# mini-v1_14-macrofab-rtg.net
KiCad netlist of a schematic drawn in EAGLE
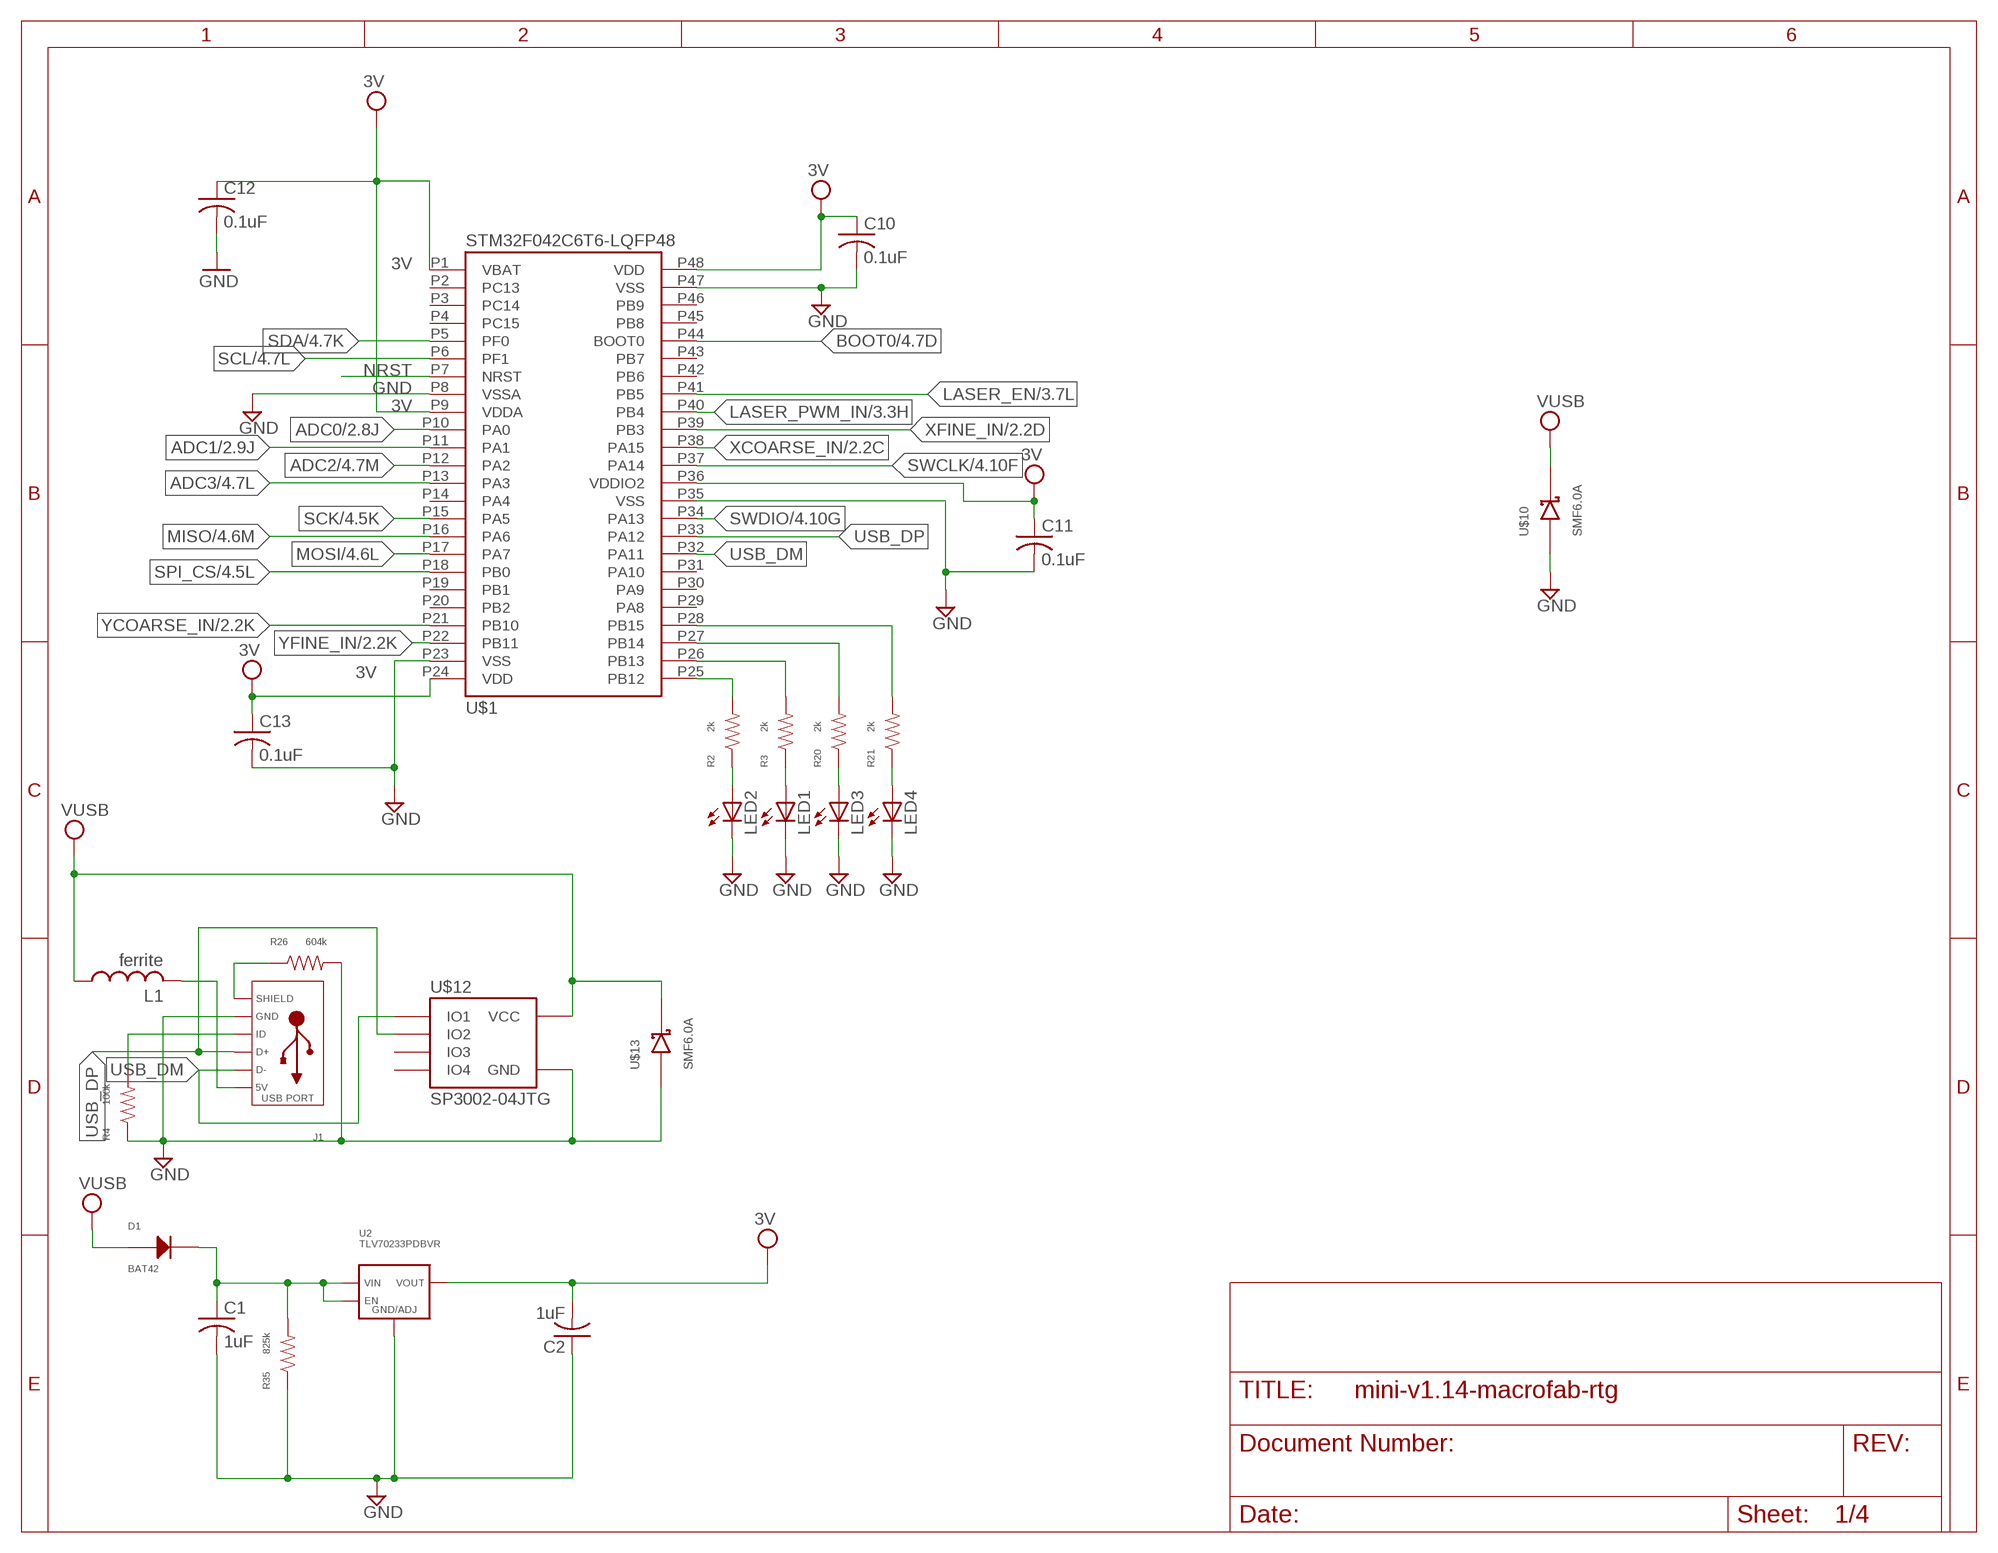
[diagram p0: schematic, sheet 1]
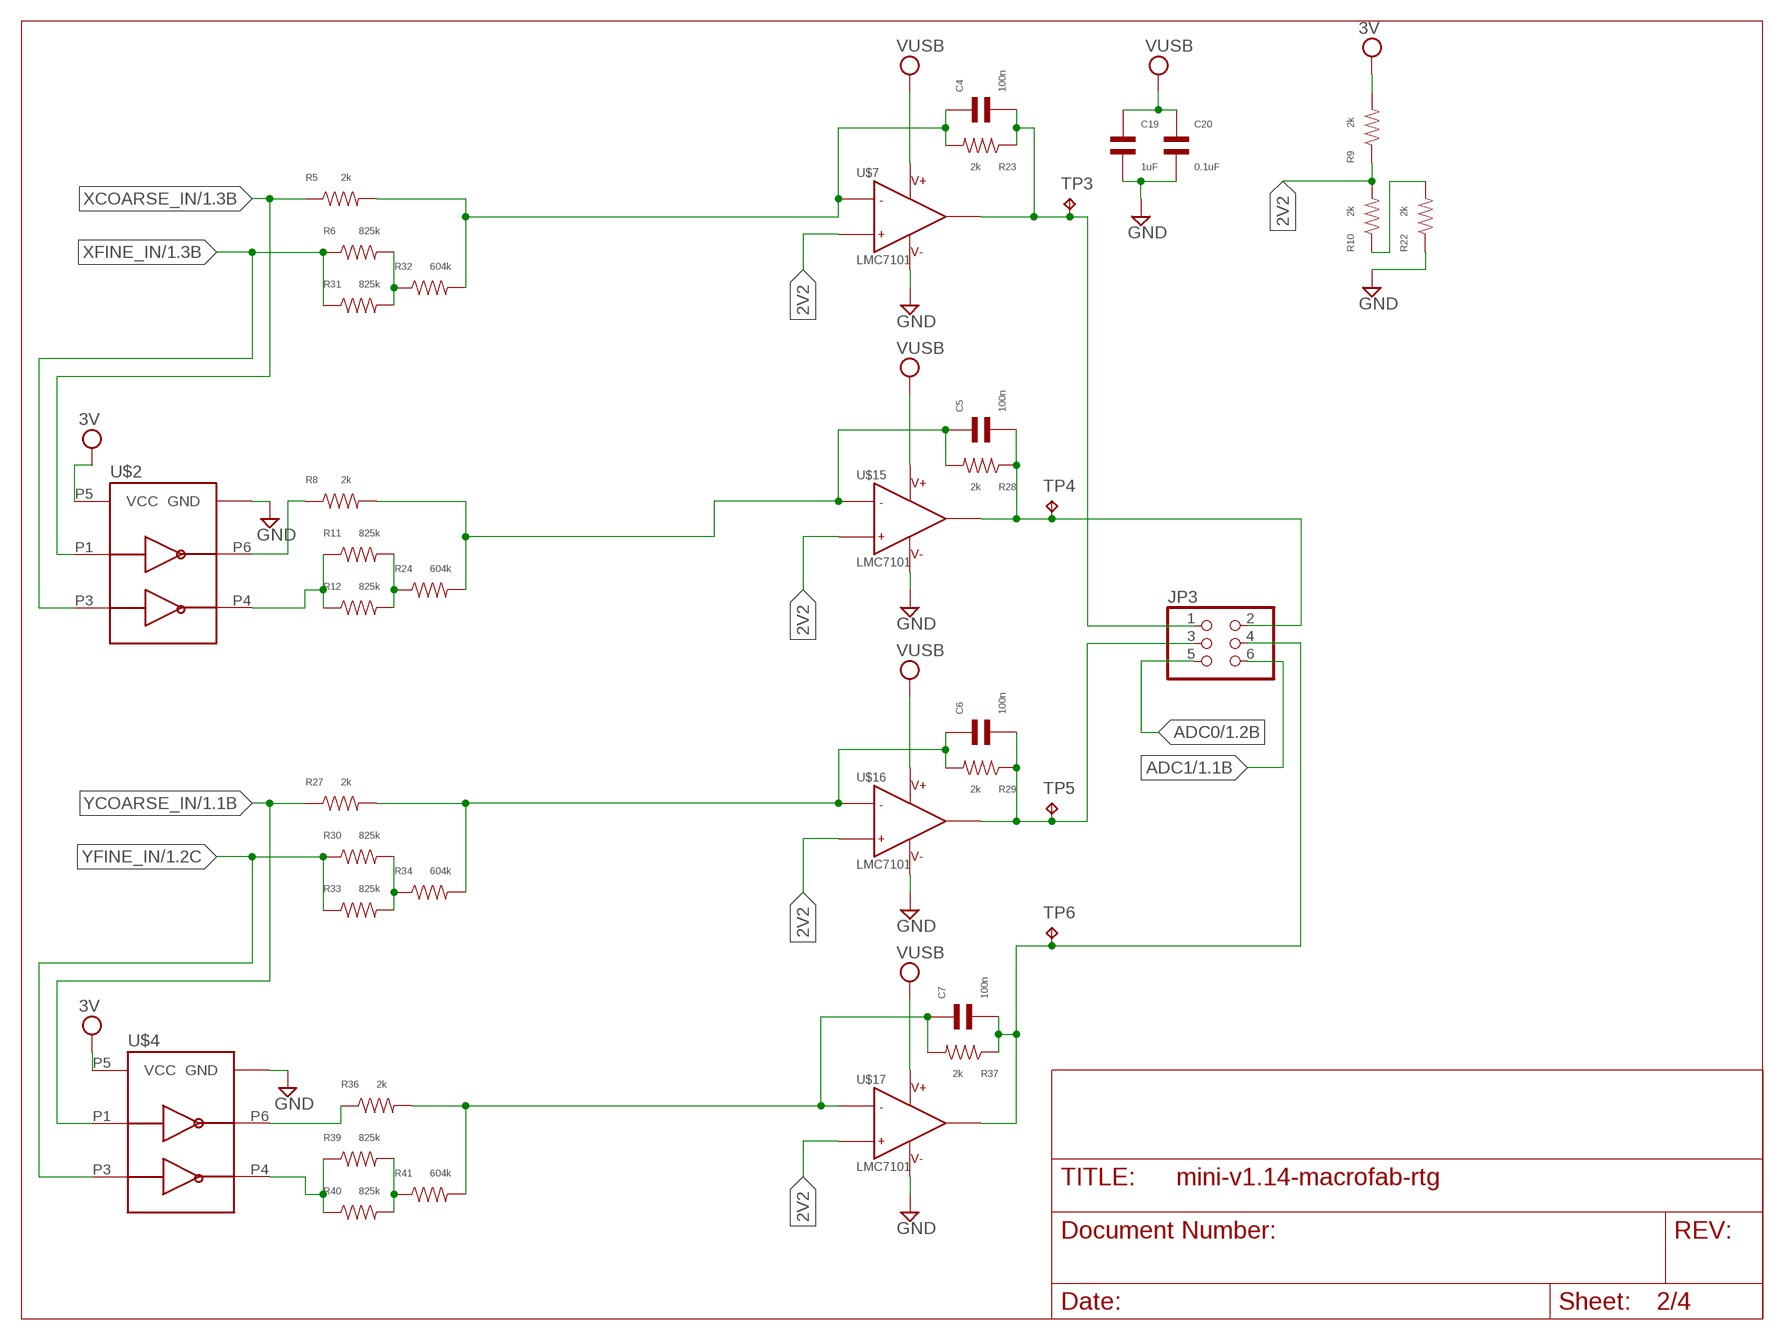
[diagram p1: schematic, sheet 2]
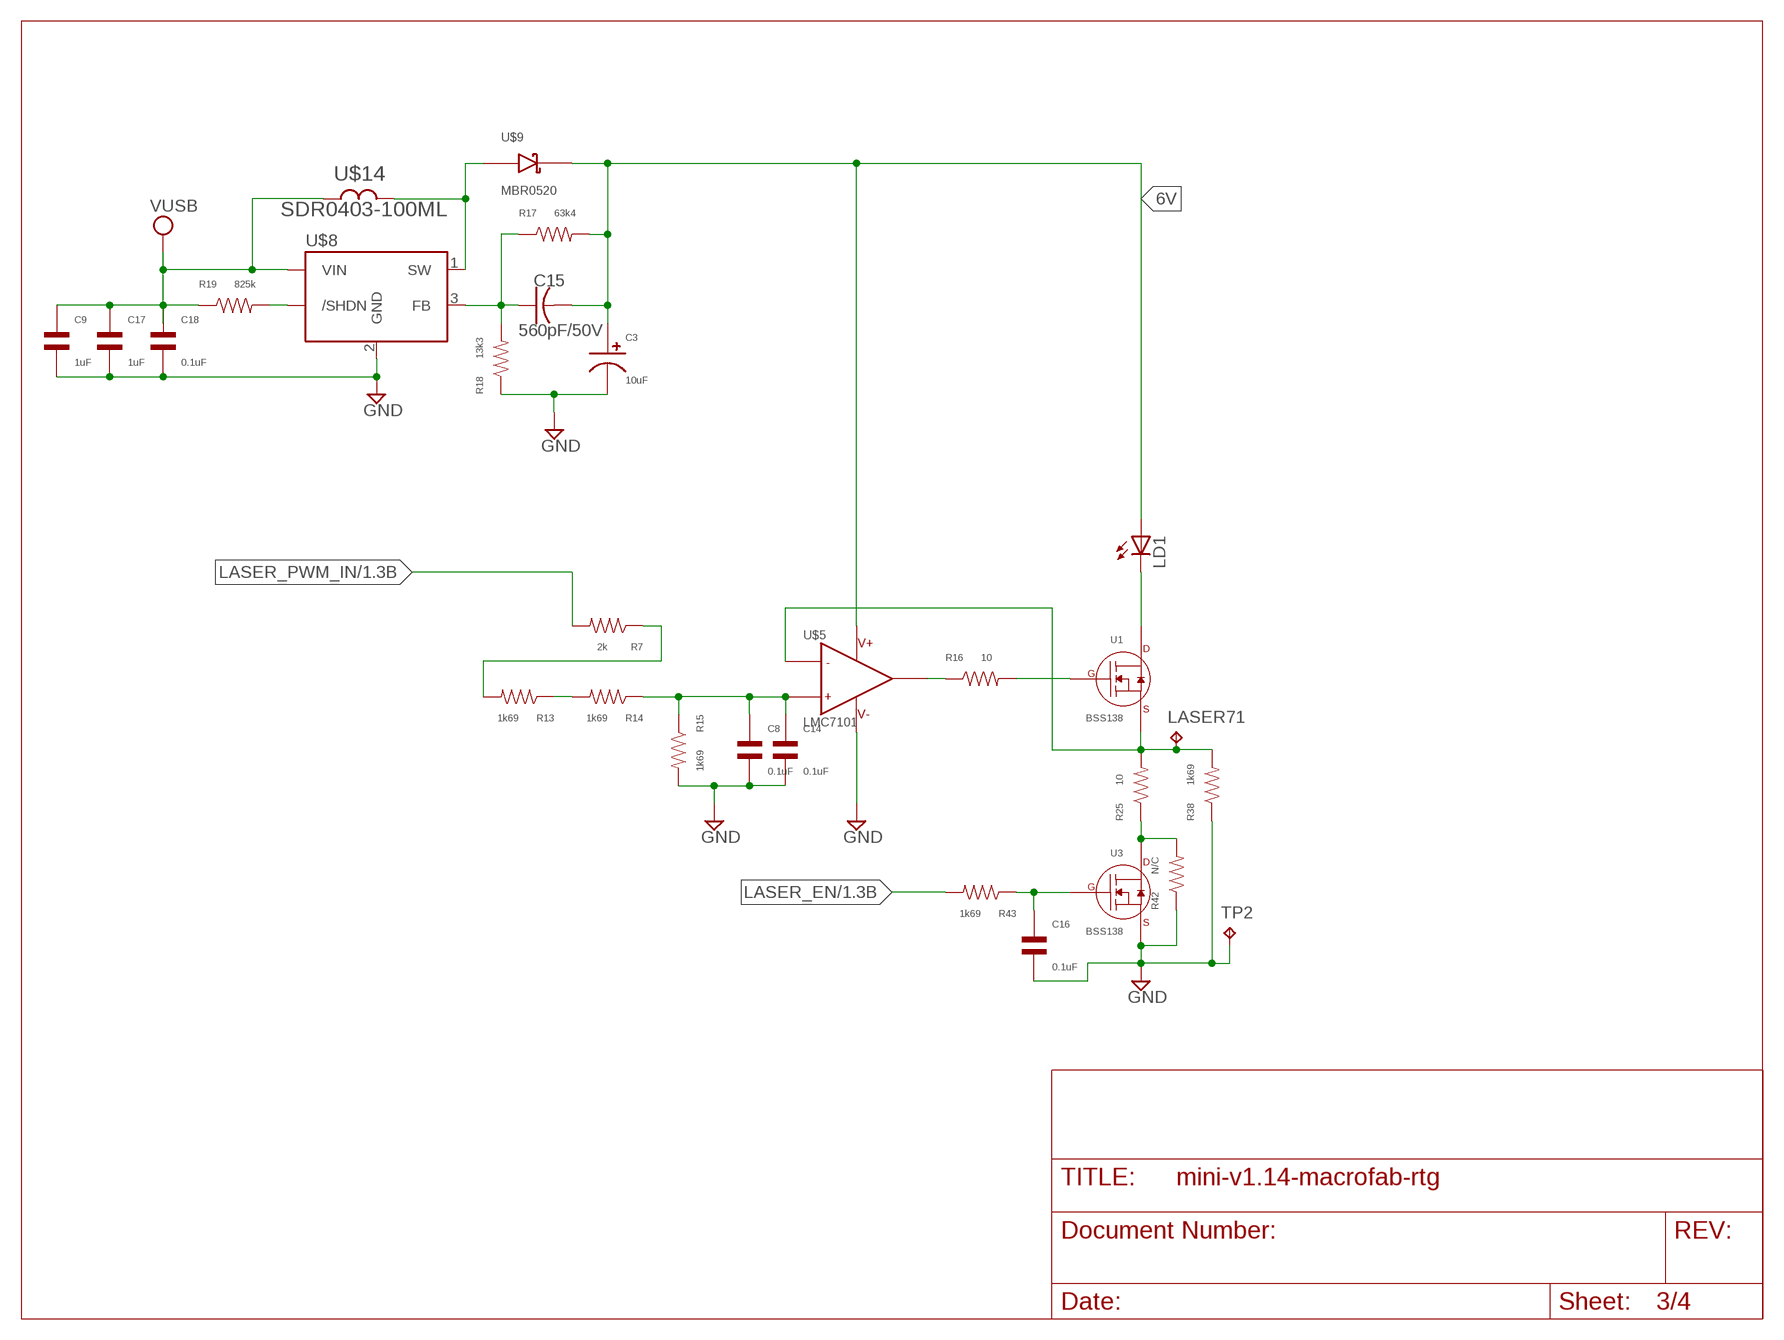
[diagram p2: schematic, sheet 3]
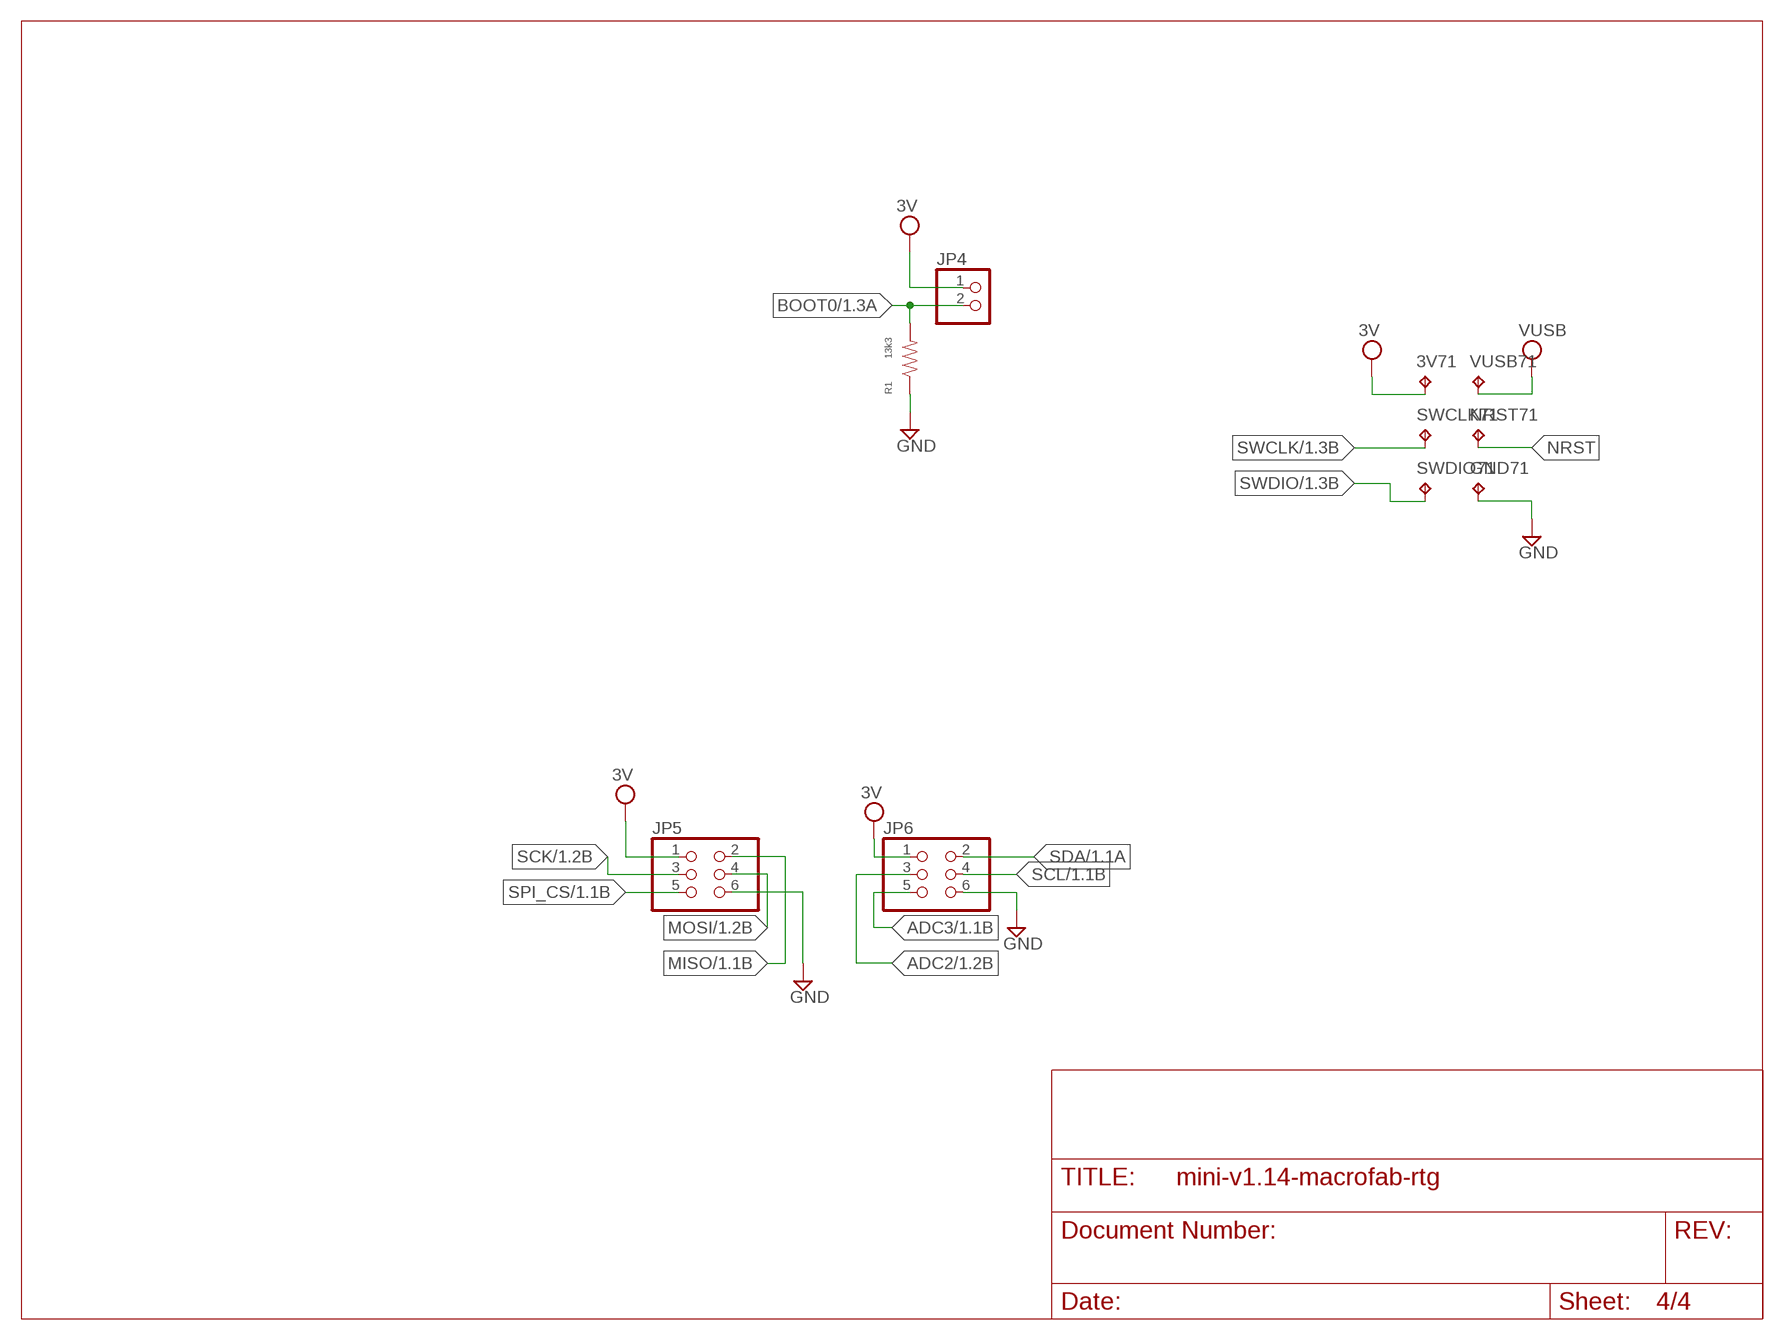
[diagram p3: schematic, sheet 4]

(export (version "E")
  (design (tool "Eeschema 10.0.6"))
  (components
    (comp (ref "3V71")
      (value "TPB1,27")
      (footprint "eagle-import:B1,27")
      (libsource (lib "eagle-import") (part "TPB1,27"))
    )
    (comp (ref "GND71")
      (value "TPB1,27")
      (footprint "eagle-import:B1,27")
      (libsource (lib "eagle-import") (part "TPB1,27"))
    )
    (comp (ref "JP4")
      (value "PINHD-1X2")
      (footprint "eagle-import:1X02")
      (libsource (lib "eagle-import") (part "PINHD-1X2"))
    )
    (comp (ref "JP5")
      (value "PINHD-2X3")
      (footprint "eagle-import:2X03")
      (libsource (lib "eagle-import") (part "PINHD-2X3"))
    )
    (comp (ref "JP6")
      (value "PINHD-2X3")
      (footprint "eagle-import:2X03")
      (libsource (lib "eagle-import") (part "PINHD-2X3"))
    )
    (comp (ref "NRST71")
      (value "TPB1,27")
      (footprint "eagle-import:B1,27")
      (libsource (lib "eagle-import") (part "TPB1,27"))
    )
    (comp (ref "R1")
      (value "13k3")
      (footprint "eagle-import:R0603")
      (libsource (lib "eagle-import") (part "RESISTOR_0603"))
    )
    (comp (ref "SWCLK71")
      (value "TPB1,27")
      (footprint "eagle-import:B1,27")
      (libsource (lib "eagle-import") (part "TPB1,27"))
    )
    (comp (ref "SWDIO71")
      (value "TPB1,27")
      (footprint "eagle-import:B1,27")
      (libsource (lib "eagle-import") (part "TPB1,27"))
    )
    (comp (ref "VUSB71")
      (value "TPB1,27")
      (footprint "eagle-import:B1,27")
      (libsource (lib "eagle-import") (part "TPB1,27"))
    )
    (comp (ref "C3")
      (value "10uF")
      (footprint "eagle-import:CP4MM")
      (libsource (lib "eagle-import") (part "CAPACITOR_P_4MM"))
    )
    (comp (ref "C8")
      (value "0.1uF")
      (footprint "eagle-import:C0603")
      (libsource (lib "eagle-import") (part "CAPACITOR_NP_0603"))
    )
    (comp (ref "C9")
      (value "1uF")
      (footprint "eagle-import:C0603")
      (libsource (lib "eagle-import") (part "CAPACITOR_NP_0603"))
    )
    (comp (ref "C14")
      (value "0.1uF")
      (footprint "eagle-import:C0603")
      (libsource (lib "eagle-import") (part "CAPACITOR_NP_0603"))
    )
    (comp (ref "C15")
      (value "560pF/50V")
      (footprint "eagle-import:C0603")
      (libsource (lib "eagle-import") (part "C-USC0603"))
    )
    (comp (ref "C16")
      (value "0.1uF")
      (footprint "eagle-import:C0603")
      (libsource (lib "eagle-import") (part "CAPACITOR_NP_0603"))
    )
    (comp (ref "C17")
      (value "1uF")
      (footprint "eagle-import:C0603")
      (libsource (lib "eagle-import") (part "CAPACITOR_NP_0603"))
    )
    (comp (ref "C18")
      (value "0.1uF")
      (footprint "eagle-import:C0603")
      (libsource (lib "eagle-import") (part "CAPACITOR_NP_0603"))
    )
    (comp (ref "LASER71")
      (value "TPB2,54")
      (footprint "eagle-import:B2,54")
      (libsource (lib "eagle-import") (part "TPB2,54"))
    )
    (comp (ref "LD1")
      (value "SCOTT_LASERDIODELD3")
      (footprint "eagle-import:SCOTT_LASERDIODE3")
      (fields (field (name "MPN") "3 x (0552-2-15-15-11-27-10-0)"))
      (libsource (lib "eagle-import") (part "SCOTT_LASERDIODELD3"))
    )
    (comp (ref "R7")
      (value "2k")
      (footprint "eagle-import:R0603")
      (libsource (lib "eagle-import") (part "RESISTOR_0603"))
    )
    (comp (ref "R13")
      (value "1k69")
      (footprint "eagle-import:R0603")
      (libsource (lib "eagle-import") (part "RESISTOR_0603"))
    )
    (comp (ref "R14")
      (value "1k69")
      (footprint "eagle-import:R0603")
      (libsource (lib "eagle-import") (part "RESISTOR_0603"))
    )
    (comp (ref "R15")
      (value "1k69")
      (footprint "eagle-import:R0603")
      (libsource (lib "eagle-import") (part "RESISTOR_0603"))
    )
    (comp (ref "R16")
      (value "10")
      (footprint "eagle-import:R0603")
      (libsource (lib "eagle-import") (part "RESISTOR_0603"))
    )
    (comp (ref "R17")
      (value "63k4")
      (footprint "eagle-import:R0603")
      (libsource (lib "eagle-import") (part "RESISTOR_0603"))
    )
    (comp (ref "R18")
      (value "13k3")
      (footprint "eagle-import:R0603")
      (libsource (lib "eagle-import") (part "RESISTOR_0603"))
    )
    (comp (ref "R19")
      (value "825k")
      (footprint "eagle-import:R0603")
      (libsource (lib "eagle-import") (part "RESISTOR_0603"))
    )
    (comp (ref "R25")
      (value "10")
      (footprint "eagle-import:R0603")
      (libsource (lib "eagle-import") (part "RESISTOR_0603"))
    )
    (comp (ref "R38")
      (value "1k69")
      (footprint "eagle-import:R0603")
      (libsource (lib "eagle-import") (part "RESISTOR_0603"))
    )
    (comp (ref "R42")
      (value "N/C")
      (footprint "eagle-import:R0603")
      (libsource (lib "eagle-import") (part "RESISTOR_0603"))
    )
    (comp (ref "R43")
      (value "1k69")
      (footprint "eagle-import:R0603")
      (libsource (lib "eagle-import") (part "RESISTOR_0603"))
    )
    (comp (ref "TP2")
      (value "GND")
      (footprint "eagle-import:B2,54")
      (libsource (lib "eagle-import") (part "TPB2,54"))
    )
    (comp (ref "U$5")
      (value "LMC7101")
      (footprint "eagle-import:SOT23-5")
      (libsource (lib "eagle-import") (part "OPAMP-SINGLELMC7101"))
    )
    (comp (ref "U$8")
      (value "LMR62014")
      (footprint "eagle-import:SOT23-5")
      (libsource (lib "eagle-import") (part "LMR62014"))
    )
    (comp (ref "U$9")
      (value "MBR0520")
      (footprint "eagle-import:SOD123")
      (libsource (lib "eagle-import") (part "MBR0520"))
    )
    (comp (ref "U$14")
      (value "SDR0403-100ML")
      (footprint "eagle-import:SDR0403")
      (libsource (lib "eagle-import") (part "SDR0403"))
    )
    (comp (ref "U1")
      (value "BSS138")
      (footprint "eagle-import:SOT-23-3")
      (libsource (lib "eagle-import") (part "N-CHANNEL_FET_SOT-23-3"))
    )
    (comp (ref "U3")
      (value "BSS138")
      (footprint "eagle-import:SOT-23-3")
      (libsource (lib "eagle-import") (part "N-CHANNEL_FET_SOT-23-3"))
    )
    (comp (ref "C4")
      (value "100n")
      (footprint "eagle-import:C0603")
      (libsource (lib "eagle-import") (part "CAPACITOR_NP_0603"))
    )
    (comp (ref "C5")
      (value "100n")
      (footprint "eagle-import:C0603")
      (libsource (lib "eagle-import") (part "CAPACITOR_NP_0603"))
    )
    (comp (ref "C6")
      (value "100n")
      (footprint "eagle-import:C0603")
      (libsource (lib "eagle-import") (part "CAPACITOR_NP_0603"))
    )
    (comp (ref "C7")
      (value "100n")
      (footprint "eagle-import:C0603")
      (libsource (lib "eagle-import") (part "CAPACITOR_NP_0603"))
    )
    (comp (ref "C19")
      (value "1uF")
      (footprint "eagle-import:C0603")
      (libsource (lib "eagle-import") (part "CAPACITOR_NP_0603"))
    )
    (comp (ref "C20")
      (value "0.1uF")
      (footprint "eagle-import:C0603")
      (libsource (lib "eagle-import") (part "CAPACITOR_NP_0603"))
    )
    (comp (ref "JP3")
      (value "PINHD-2X3")
      (footprint "eagle-import:2X03")
      (libsource (lib "eagle-import") (part "PINHD-2X3"))
    )
    (comp (ref "R5")
      (value "2k")
      (footprint "eagle-import:R0603")
      (libsource (lib "eagle-import") (part "RESISTOR_0603"))
    )
    (comp (ref "R6")
      (value "825k")
      (footprint "eagle-import:R0603")
      (libsource (lib "eagle-import") (part "RESISTOR_0603"))
    )
    (comp (ref "R8")
      (value "2k")
      (footprint "eagle-import:R0603")
      (libsource (lib "eagle-import") (part "RESISTOR_0603"))
    )
    (comp (ref "R9")
      (value "2k")
      (footprint "eagle-import:R0603")
      (libsource (lib "eagle-import") (part "RESISTOR_0603"))
    )
    (comp (ref "R10")
      (value "2k")
      (footprint "eagle-import:R0603")
      (libsource (lib "eagle-import") (part "RESISTOR_0603"))
    )
    (comp (ref "R11")
      (value "825k")
      (footprint "eagle-import:R0603")
      (libsource (lib "eagle-import") (part "RESISTOR_0603"))
    )
    (comp (ref "R12")
      (value "825k")
      (footprint "eagle-import:R0603")
      (libsource (lib "eagle-import") (part "RESISTOR_0603"))
    )
    (comp (ref "R22")
      (value "2k")
      (footprint "eagle-import:R0603")
      (libsource (lib "eagle-import") (part "RESISTOR_0603"))
    )
    (comp (ref "R23")
      (value "2k")
      (footprint "eagle-import:R0603")
      (libsource (lib "eagle-import") (part "RESISTOR_0603"))
    )
    (comp (ref "R24")
      (value "604k")
      (footprint "eagle-import:R0603")
      (libsource (lib "eagle-import") (part "RESISTOR_0603"))
    )
    (comp (ref "R27")
      (value "2k")
      (footprint "eagle-import:R0603")
      (libsource (lib "eagle-import") (part "RESISTOR_0603"))
    )
    (comp (ref "R28")
      (value "2k")
      (footprint "eagle-import:R0603")
      (libsource (lib "eagle-import") (part "RESISTOR_0603"))
    )
    (comp (ref "R29")
      (value "2k")
      (footprint "eagle-import:R0603")
      (libsource (lib "eagle-import") (part "RESISTOR_0603"))
    )
    (comp (ref "R30")
      (value "825k")
      (footprint "eagle-import:R0603")
      (libsource (lib "eagle-import") (part "RESISTOR_0603"))
    )
    (comp (ref "R31")
      (value "825k")
      (footprint "eagle-import:R0603")
      (libsource (lib "eagle-import") (part "RESISTOR_0603"))
    )
    (comp (ref "R32")
      (value "604k")
      (footprint "eagle-import:R0603")
      (libsource (lib "eagle-import") (part "RESISTOR_0603"))
    )
    (comp (ref "R33")
      (value "825k")
      (footprint "eagle-import:R0603")
      (libsource (lib "eagle-import") (part "RESISTOR_0603"))
    )
    (comp (ref "R34")
      (value "604k")
      (footprint "eagle-import:R0603")
      (libsource (lib "eagle-import") (part "RESISTOR_0603"))
    )
    (comp (ref "R36")
      (value "2k")
      (footprint "eagle-import:R0603")
      (libsource (lib "eagle-import") (part "RESISTOR_0603"))
    )
    (comp (ref "R37")
      (value "2k")
      (footprint "eagle-import:R0603")
      (libsource (lib "eagle-import") (part "RESISTOR_0603"))
    )
    (comp (ref "R39")
      (value "825k")
      (footprint "eagle-import:R0603")
      (libsource (lib "eagle-import") (part "RESISTOR_0603"))
    )
    (comp (ref "R40")
      (value "825k")
      (footprint "eagle-import:R0603")
      (libsource (lib "eagle-import") (part "RESISTOR_0603"))
    )
    (comp (ref "R41")
      (value "604k")
      (footprint "eagle-import:R0603")
      (libsource (lib "eagle-import") (part "RESISTOR_0603"))
    )
    (comp (ref "TP3")
      (value "TPB1,27")
      (footprint "eagle-import:B1,27")
      (libsource (lib "eagle-import") (part "TPB1,27"))
    )
    (comp (ref "TP4")
      (value "TPB1,27")
      (footprint "eagle-import:B1,27")
      (libsource (lib "eagle-import") (part "TPB1,27"))
    )
    (comp (ref "TP5")
      (value "TPB1,27")
      (footprint "eagle-import:B1,27")
      (libsource (lib "eagle-import") (part "TPB1,27"))
    )
    (comp (ref "TP6")
      (value "TPB1,27")
      (footprint "eagle-import:B1,27")
      (libsource (lib "eagle-import") (part "TPB1,27"))
    )
    (comp (ref "U$2")
      (value "NC7WZ14P6X")
      (footprint "eagle-import:SC70-6")
      (libsource (lib "eagle-import") (part "NC7WZ14P6X"))
    )
    (comp (ref "U$4")
      (value "NC7WZ14P6X")
      (footprint "eagle-import:SC70-6")
      (libsource (lib "eagle-import") (part "NC7WZ14P6X"))
    )
    (comp (ref "U$7")
      (value "LMC7101")
      (footprint "eagle-import:SOT23-5")
      (libsource (lib "eagle-import") (part "LMC7101"))
    )
    (comp (ref "U$15")
      (value "LMC7101")
      (footprint "eagle-import:SOT23-5")
      (libsource (lib "eagle-import") (part "LMC7101"))
    )
    (comp (ref "U$16")
      (value "LMC7101")
      (footprint "eagle-import:SOT23-5")
      (libsource (lib "eagle-import") (part "LMC7101"))
    )
    (comp (ref "U$17")
      (value "LMC7101")
      (footprint "eagle-import:SOT23-5")
      (libsource (lib "eagle-import") (part "LMC7101"))
    )
    (comp (ref "C1")
      (value "1uF")
      (footprint "eagle-import:C0603")
      (libsource (lib "eagle-import") (part "C-USC0603"))
    )
    (comp (ref "C2")
      (value "1uF")
      (footprint "eagle-import:C0603")
      (libsource (lib "eagle-import") (part "C-USC0603"))
    )
    (comp (ref "C10")
      (value "0.1uF")
      (footprint "eagle-import:C0603")
      (libsource (lib "eagle-import") (part "C-USC0603"))
    )
    (comp (ref "C11")
      (value "0.1uF")
      (footprint "eagle-import:C0603")
      (libsource (lib "eagle-import") (part "C-USC0603"))
    )
    (comp (ref "C12")
      (value "0.1uF")
      (footprint "eagle-import:C0603")
      (libsource (lib "eagle-import") (part "C-USC0603"))
    )
    (comp (ref "C13")
      (value "0.1uF")
      (footprint "eagle-import:C0603")
      (libsource (lib "eagle-import") (part "C-USC0603"))
    )
    (comp (ref "D1")
      (value "BAT42")
      (footprint "eagle-import:SOD-123")
      (libsource (lib "eagle-import") (part "DIODE_SOD-123"))
    )
    (comp (ref "J1")
      (value "USB_MICRO_RIGHT")
      (footprint "eagle-import:MICROUSB-RIGHT")
      (libsource (lib "eagle-import") (part "USB_MICRO_RIGHT"))
    )
    (comp (ref "L1")
      (value "ferrite")
      (footprint "eagle-import:C0603")
      (libsource (lib "eagle-import") (part "L-US"))
    )
    (comp (ref "LED1")
      (value "LEDCHIP-LED0603")
      (footprint "eagle-import:CHIP-LED0603")
      (libsource (lib "eagle-import") (part "LEDCHIP-LED0603"))
    )
    (comp (ref "LED2")
      (value "LEDCHIP-LED0603")
      (footprint "eagle-import:CHIP-LED0603")
      (libsource (lib "eagle-import") (part "LEDCHIP-LED0603"))
    )
    (comp (ref "LED3")
      (value "LEDCHIP-LED0603")
      (footprint "eagle-import:CHIP-LED0603")
      (libsource (lib "eagle-import") (part "LEDCHIP-LED0603"))
    )
    (comp (ref "LED4")
      (value "LEDCHIP-LED0603")
      (footprint "eagle-import:CHIP-LED0603")
      (libsource (lib "eagle-import") (part "LEDCHIP-LED0603"))
    )
    (comp (ref "R2")
      (value "2k")
      (footprint "eagle-import:R0603")
      (libsource (lib "eagle-import") (part "RESISTOR_0603"))
    )
    (comp (ref "R3")
      (value "2k")
      (footprint "eagle-import:R0603")
      (libsource (lib "eagle-import") (part "RESISTOR_0603"))
    )
    (comp (ref "R4")
      (value "100k")
      (footprint "eagle-import:R0603")
      (libsource (lib "eagle-import") (part "RESISTOR_0603"))
    )
    (comp (ref "R20")
      (value "2k")
      (footprint "eagle-import:R0603")
      (libsource (lib "eagle-import") (part "RESISTOR_0603"))
    )
    (comp (ref "R21")
      (value "2k")
      (footprint "eagle-import:R0603")
      (libsource (lib "eagle-import") (part "RESISTOR_0603"))
    )
    (comp (ref "R26")
      (value "604k")
      (footprint "eagle-import:R0603")
      (libsource (lib "eagle-import") (part "RESISTOR_0603"))
    )
    (comp (ref "R35")
      (value "825k")
      (footprint "eagle-import:R0603")
      (libsource (lib "eagle-import") (part "RESISTOR_0603"))
    )
    (comp (ref "U$1")
      (value "STM32F042C6T6-LQFP48")
      (footprint "eagle-import:LQFP48")
      (libsource (lib "eagle-import") (part "STM32F042-LQFP48"))
    )
    (comp (ref "U$10")
      (value "SMF6.0A")
      (footprint "eagle-import:SOD123")
      (libsource (lib "eagle-import") (part "MBR0520"))
    )
    (comp (ref "U$12")
      (value "SP3002-04JTG")
      (footprint "eagle-import:SC70-6")
      (libsource (lib "eagle-import") (part "SP3002"))
    )
    (comp (ref "U$13")
      (value "SMF6.0A")
      (footprint "eagle-import:SOD123")
      (libsource (lib "eagle-import") (part "MBR0520"))
    )
    (comp (ref "U2")
      (value "TLV70233PDBVR")
      (footprint "eagle-import:SOT-23-5")
      (libsource (lib "eagle-import") (part "TLV70233PDBVR"))
    )
  )
  (nets
    (net (code "1") (name "2V2") (class "Default")
      (node (ref "R10") (pin "P$2") (pinfunction "P$2_P$2") (pintype "passive"))
      (node (ref "R9") (pin "P$1") (pinfunction "P$1_P$1") (pintype "passive"))
      (node (ref "U$15") (pin "3") (pinfunction "P3_3") (pintype "bidirectional"))
      (node (ref "U$16") (pin "3") (pinfunction "P3_3") (pintype "bidirectional"))
      (node (ref "U$17") (pin "3") (pinfunction "P3_3") (pintype "bidirectional"))
      (node (ref "U$7") (pin "3") (pinfunction "P3_3") (pintype "bidirectional"))
    )
    (net (code "2") (name "3V") (class "Default")
      (node (ref "3V71") (pin "TP") (pinfunction "TP_TP") (pintype "input"))
      (node (ref "C10") (pin "1") (pinfunction "1_1") (pintype "passive"))
      (node (ref "C11") (pin "1") (pinfunction "1_1") (pintype "passive"))
      (node (ref "C12") (pin "1") (pinfunction "1_1") (pintype "passive"))
      (node (ref "C13") (pin "1") (pinfunction "1_1") (pintype "passive"))
      (node (ref "C2") (pin "2") (pinfunction "2_2") (pintype "passive"))
      (node (ref "JP4") (pin "1") (pinfunction "1_1") (pintype "passive"))
      (node (ref "JP5") (pin "1") (pinfunction "1_1") (pintype "passive"))
      (node (ref "JP6") (pin "1") (pinfunction "1_1") (pintype "passive"))
      (node (ref "R9") (pin "P$2") (pinfunction "P$2_P$2") (pintype "passive"))
      (node (ref "U$1") (pin "P1") (pinfunction "VBAT_P1") (pintype "bidirectional"))
      (node (ref "U$1") (pin "P24") (pinfunction "VDD_P24") (pintype "bidirectional"))
      (node (ref "U$1") (pin "P36") (pinfunction "VDDIO2_P36") (pintype "bidirectional"))
      (node (ref "U$1") (pin "P48") (pinfunction "VDD_P48") (pintype "bidirectional"))
      (node (ref "U$1") (pin "P9") (pinfunction "VDDA_P9") (pintype "bidirectional"))
      (node (ref "U$2") (pin "P5") (pinfunction "VCC_P5") (pintype "power_in"))
      (node (ref "U$4") (pin "P5") (pinfunction "VCC_P5") (pintype "power_in"))
      (node (ref "U2") (pin "P$5") (pinfunction "VOUT_P$5") (pintype "bidirectional"))
    )
    (net (code "3") (name "6V") (class "Default")
      (node (ref "C15") (pin "2") (pinfunction "2_2") (pintype "passive"))
      (node (ref "C3") (pin "P$1") (pinfunction "P$1_P$1") (pintype "passive"))
      (node (ref "LD1") (pin "P$1") (pinfunction "A_P$1") (pintype "passive"))
      (node (ref "R17") (pin "P$2") (pinfunction "P$2_P$2") (pintype "passive"))
      (node (ref "U$5") (pin "2") (pinfunction "V+_2") (pintype "power_in"))
      (node (ref "U$9") (pin "CATHODE") (pinfunction "CATHODE_CATHODE") (pintype "bidirectional"))
    )
    (net (code "4") (name "ADC0") (class "Default")
      (node (ref "JP3") (pin "5") (pinfunction "5_5") (pintype "passive"))
      (node (ref "U$1") (pin "P10") (pinfunction "PA0_P10") (pintype "bidirectional"))
    )
    (net (code "5") (name "ADC1") (class "Default")
      (node (ref "JP3") (pin "6") (pinfunction "6_6") (pintype "passive"))
      (node (ref "U$1") (pin "P11") (pinfunction "PA1_P11") (pintype "bidirectional"))
    )
    (net (code "6") (name "ADC2") (class "Default")
      (node (ref "JP6") (pin "3") (pinfunction "3_3") (pintype "passive"))
      (node (ref "U$1") (pin "P12") (pinfunction "PA2_P12") (pintype "bidirectional"))
    )
    (net (code "7") (name "ADC3") (class "Default")
      (node (ref "JP6") (pin "5") (pinfunction "5_5") (pintype "passive"))
      (node (ref "U$1") (pin "P13") (pinfunction "PA3_P13") (pintype "bidirectional"))
    )
    (net (code "8") (name "BOOT0") (class "Default")
      (node (ref "JP4") (pin "2") (pinfunction "2_2") (pintype "passive"))
      (node (ref "R1") (pin "P$2") (pinfunction "P$2_P$2") (pintype "passive"))
      (node (ref "U$1") (pin "P44") (pinfunction "BOOT0_P44") (pintype "bidirectional"))
    )
    (net (code "9") (name "GND") (class "Default")
      (node (ref "C1") (pin "2") (pinfunction "2_2") (pintype "passive"))
      (node (ref "C10") (pin "2") (pinfunction "2_2") (pintype "passive"))
      (node (ref "C11") (pin "2") (pinfunction "2_2") (pintype "passive"))
      (node (ref "C12") (pin "2") (pinfunction "2_2") (pintype "passive"))
      (node (ref "C13") (pin "2") (pinfunction "2_2") (pintype "passive"))
      (node (ref "C14") (pin "P$2") (pinfunction "P$2_P$2") (pintype "passive"))
      (node (ref "C16") (pin "P$2") (pinfunction "P$2_P$2") (pintype "passive"))
      (node (ref "C17") (pin "P$2") (pinfunction "P$2_P$2") (pintype "passive"))
      (node (ref "C18") (pin "P$2") (pinfunction "P$2_P$2") (pintype "passive"))
      (node (ref "C19") (pin "P$2") (pinfunction "P$2_P$2") (pintype "passive"))
      (node (ref "C2") (pin "1") (pinfunction "1_1") (pintype "passive"))
      (node (ref "C20") (pin "P$2") (pinfunction "P$2_P$2") (pintype "passive"))
      (node (ref "C3") (pin "P$2") (pinfunction "P$2_P$2") (pintype "passive"))
      (node (ref "C8") (pin "P$2") (pinfunction "P$2_P$2") (pintype "passive"))
      (node (ref "C9") (pin "P$2") (pinfunction "P$2_P$2") (pintype "passive"))
      (node (ref "GND71") (pin "TP") (pinfunction "TP_TP") (pintype "input"))
      (node (ref "J1") (pin "5") (pinfunction "GND_5") (pintype "power_in"))
      (node (ref "JP5") (pin "6") (pinfunction "6_6") (pintype "passive"))
      (node (ref "JP6") (pin "6") (pinfunction "6_6") (pintype "passive"))
      (node (ref "LED1") (pin "C") (pinfunction "C_C") (pintype "passive"))
      (node (ref "LED2") (pin "C") (pinfunction "C_C") (pintype "passive"))
      (node (ref "LED3") (pin "C") (pinfunction "C_C") (pintype "passive"))
      (node (ref "LED4") (pin "C") (pinfunction "C_C") (pintype "passive"))
      (node (ref "R1") (pin "P$1") (pinfunction "P$1_P$1") (pintype "passive"))
      (node (ref "R15") (pin "P$2") (pinfunction "P$2_P$2") (pintype "passive"))
      (node (ref "R18") (pin "P$1") (pinfunction "P$1_P$1") (pintype "passive"))
      (node (ref "R22") (pin "P$1") (pinfunction "P$1_P$1") (pintype "passive"))
      (node (ref "R26") (pin "P$2") (pinfunction "P$2_P$2") (pintype "passive"))
      (node (ref "R35") (pin "P$1") (pinfunction "P$1_P$1") (pintype "passive"))
      (node (ref "R38") (pin "P$1") (pinfunction "P$1_P$1") (pintype "passive"))
      (node (ref "R4") (pin "P$1") (pinfunction "P$1_P$1") (pintype "passive"))
      (node (ref "R42") (pin "P$1") (pinfunction "P$1_P$1") (pintype "passive"))
      (node (ref "TP2") (pin "TP") (pinfunction "TP_TP") (pintype "input"))
      (node (ref "U$1") (pin "P23") (pinfunction "VSS_P23") (pintype "bidirectional"))
      (node (ref "U$1") (pin "P35") (pinfunction "VSS_P35") (pintype "bidirectional"))
      (node (ref "U$1") (pin "P47") (pinfunction "VSS_P47") (pintype "bidirectional"))
      (node (ref "U$1") (pin "P8") (pinfunction "VSSA_P8") (pintype "bidirectional"))
      (node (ref "U$10") (pin "ANODE") (pinfunction "ANODE_ANODE") (pintype "bidirectional"))
      (node (ref "U$12") (pin "P2") (pinfunction "GND_P2") (pintype "power_in"))
      (node (ref "U$13") (pin "ANODE") (pinfunction "ANODE_ANODE") (pintype "bidirectional"))
      (node (ref "U$15") (pin "5") (pinfunction "P5_5") (pintype "power_in"))
      (node (ref "U$16") (pin "5") (pinfunction "P5_5") (pintype "power_in"))
      (node (ref "U$17") (pin "5") (pinfunction "P5_5") (pintype "power_in"))
      (node (ref "U$2") (pin "P2") (pinfunction "GND_P2") (pintype "power_in"))
      (node (ref "U$4") (pin "P2") (pinfunction "GND_P2") (pintype "power_in"))
      (node (ref "U$5") (pin "5") (pinfunction "V-_5") (pintype "power_in"))
      (node (ref "U$7") (pin "5") (pinfunction "P5_5") (pintype "power_in"))
      (node (ref "U$8") (pin "2") (pinfunction "GND_2") (pintype "bidirectional"))
      (node (ref "U2") (pin "P$2") (pinfunction "GND/ADJ_P$2") (pintype "bidirectional"))
      (node (ref "U3") (pin "P$2") (pinfunction "SOURCE_P$2") (pintype "bidirectional"))
    )
    (net (code "10") (name "LASER_EN") (class "Default")
      (node (ref "R43") (pin "P$2") (pinfunction "P$2_P$2") (pintype "passive"))
      (node (ref "U$1") (pin "P41") (pinfunction "PB5_P41") (pintype "bidirectional"))
    )
    (net (code "11") (name "LASER_PWM_IN") (class "Default")
      (node (ref "R7") (pin "P$2") (pinfunction "P$2_P$2") (pintype "passive"))
      (node (ref "U$1") (pin "P40") (pinfunction "PB4_P40") (pintype "bidirectional"))
    )
    (net (code "12") (name "MISO") (class "Default")
      (node (ref "JP5") (pin "2") (pinfunction "2_2") (pintype "passive"))
      (node (ref "U$1") (pin "P16") (pinfunction "PA6_P16") (pintype "bidirectional"))
    )
    (net (code "13") (name "MOSI") (class "Default")
      (node (ref "JP5") (pin "4") (pinfunction "4_4") (pintype "passive"))
      (node (ref "U$1") (pin "P17") (pinfunction "PA7_P17") (pintype "bidirectional"))
    )
    (net (code "14") (name "NRST") (class "Default")
      (node (ref "NRST71") (pin "TP") (pinfunction "TP_TP") (pintype "input"))
      (node (ref "U$1") (pin "P7") (pinfunction "NRST_P7") (pintype "bidirectional"))
    )
    (net (code "15") (name "Net-(J1-5V)") (class "Default")
      (node (ref "J1") (pin "1") (pinfunction "5V_1") (pintype "power_in"))
      (node (ref "L1") (pin "2") (pinfunction "2_2") (pintype "passive"))
    )
    (net (code "16") (name "Net-(J1-ID)") (class "Default")
      (node (ref "J1") (pin "4") (pinfunction "ID_4") (pintype "bidirectional"))
      (node (ref "R4") (pin "P$2") (pinfunction "P$2_P$2") (pintype "passive"))
    )
    (net (code "17") (name "Net-(J1-SLD-PadS1)") (class "Default")
      (node (ref "J1") (pin "S1") (pinfunction "SLD_S1") (pintype "power_in"))
      (node (ref "J1") (pin "S2") (pinfunction "SLD_S2") (pintype "power_in"))
      (node (ref "J1") (pin "S3") (pinfunction "SLD_S3") (pintype "power_in"))
      (node (ref "J1") (pin "S4") (pinfunction "SLD_S4") (pintype "power_in"))
      (node (ref "J1") (pin "S5") (pinfunction "SLD_S5") (pintype "power_in"))
      (node (ref "J1") (pin "S6") (pinfunction "SLD_S6") (pintype "power_in"))
      (node (ref "R26") (pin "P$1") (pinfunction "P$1_P$1") (pintype "passive"))
    )
    (net (code "18") (name "Net-(LD1-C)") (class "Default")
      (node (ref "LD1") (pin "P$3") (pinfunction "C_P$3") (pintype "passive"))
      (node (ref "U1") (pin "P$3") (pinfunction "DRAIN_P$3") (pintype "bidirectional"))
    )
    (net (code "19") (name "Net-(LED1-PadA)") (class "Default")
      (node (ref "LED1") (pin "A") (pinfunction "A_A") (pintype "passive"))
      (node (ref "R3") (pin "P$1") (pinfunction "P$1_P$1") (pintype "passive"))
    )
    (net (code "20") (name "Net-(LED2-PadA)") (class "Default")
      (node (ref "LED2") (pin "A") (pinfunction "A_A") (pintype "passive"))
      (node (ref "R2") (pin "P$1") (pinfunction "P$1_P$1") (pintype "passive"))
    )
    (net (code "21") (name "Net-(LED3-PadA)") (class "Default")
      (node (ref "LED3") (pin "A") (pinfunction "A_A") (pintype "passive"))
      (node (ref "R20") (pin "P$1") (pinfunction "P$1_P$1") (pintype "passive"))
    )
    (net (code "22") (name "Net-(LED4-PadA)") (class "Default")
      (node (ref "LED4") (pin "A") (pinfunction "A_A") (pintype "passive"))
      (node (ref "R21") (pin "P$1") (pinfunction "P$1_P$1") (pintype "passive"))
    )
    (net (code "23") (name "Net-(R10-PadP$1)") (class "Default")
      (node (ref "R10") (pin "P$1") (pinfunction "P$1_P$1") (pintype "passive"))
      (node (ref "R22") (pin "P$2") (pinfunction "P$2_P$2") (pintype "passive"))
    )
    (net (code "24") (name "Net-(R11-PadP$2)") (class "Default")
      (node (ref "R11") (pin "P$2") (pinfunction "P$2_P$2") (pintype "passive"))
      (node (ref "R12") (pin "P$2") (pinfunction "P$2_P$2") (pintype "passive"))
      (node (ref "R24") (pin "P$1") (pinfunction "P$1_P$1") (pintype "passive"))
    )
    (net (code "25") (name "Net-(R13-PadP$1)") (class "Default")
      (node (ref "R13") (pin "P$1") (pinfunction "P$1_P$1") (pintype "passive"))
      (node (ref "R14") (pin "P$2") (pinfunction "P$2_P$2") (pintype "passive"))
    )
    (net (code "26") (name "Net-(R13-PadP$2)") (class "Default")
      (node (ref "R13") (pin "P$2") (pinfunction "P$2_P$2") (pintype "passive"))
      (node (ref "R7") (pin "P$1") (pinfunction "P$1_P$1") (pintype "passive"))
    )
    (net (code "27") (name "Net-(R30-PadP$2)") (class "Default")
      (node (ref "R30") (pin "P$2") (pinfunction "P$2_P$2") (pintype "passive"))
      (node (ref "R33") (pin "P$2") (pinfunction "P$2_P$2") (pintype "passive"))
      (node (ref "R34") (pin "P$1") (pinfunction "P$1_P$1") (pintype "passive"))
    )
    (net (code "28") (name "Net-(R31-PadP$2)") (class "Default")
      (node (ref "R31") (pin "P$2") (pinfunction "P$2_P$2") (pintype "passive"))
      (node (ref "R32") (pin "P$1") (pinfunction "P$1_P$1") (pintype "passive"))
      (node (ref "R6") (pin "P$2") (pinfunction "P$2_P$2") (pintype "passive"))
    )
    (net (code "29") (name "Net-(R39-PadP$2)") (class "Default")
      (node (ref "R39") (pin "P$2") (pinfunction "P$2_P$2") (pintype "passive"))
      (node (ref "R40") (pin "P$2") (pinfunction "P$2_P$2") (pintype "passive"))
      (node (ref "R41") (pin "P$1") (pinfunction "P$1_P$1") (pintype "passive"))
    )
    (net (code "30") (name "Net-(U$1-PB12)") (class "Default")
      (node (ref "R2") (pin "P$2") (pinfunction "P$2_P$2") (pintype "passive"))
      (node (ref "U$1") (pin "P25") (pinfunction "PB12_P25") (pintype "bidirectional"))
    )
    (net (code "31") (name "Net-(U$1-PB13)") (class "Default")
      (node (ref "R3") (pin "P$2") (pinfunction "P$2_P$2") (pintype "passive"))
      (node (ref "U$1") (pin "P26") (pinfunction "PB13_P26") (pintype "bidirectional"))
    )
    (net (code "32") (name "Net-(U$1-PB14)") (class "Default")
      (node (ref "R20") (pin "P$2") (pinfunction "P$2_P$2") (pintype "passive"))
      (node (ref "U$1") (pin "P27") (pinfunction "PB14_P27") (pintype "bidirectional"))
    )
    (net (code "33") (name "Net-(U$1-PB15)") (class "Default")
      (node (ref "R21") (pin "P$2") (pinfunction "P$2_P$2") (pintype "passive"))
      (node (ref "U$1") (pin "P28") (pinfunction "PB15_P28") (pintype "bidirectional"))
    )
    (net (code "34") (name "Net-(U$2-Y1)") (class "Default")
      (node (ref "R8") (pin "P$1") (pinfunction "P$1_P$1") (pintype "passive"))
      (node (ref "U$2") (pin "P6") (pinfunction "Y1_P6") (pintype "output"))
    )
    (net (code "35") (name "Net-(U$2-Y2)") (class "Default")
      (node (ref "R11") (pin "P$1") (pinfunction "P$1_P$1") (pintype "passive"))
      (node (ref "R12") (pin "P$1") (pinfunction "P$1_P$1") (pintype "passive"))
      (node (ref "U$2") (pin "P4") (pinfunction "Y2_P4") (pintype "output"))
    )
    (net (code "36") (name "Net-(U$4-Y1)") (class "Default")
      (node (ref "R36") (pin "P$1") (pinfunction "P$1_P$1") (pintype "passive"))
      (node (ref "U$4") (pin "P6") (pinfunction "Y1_P6") (pintype "output"))
    )
    (net (code "37") (name "Net-(U$4-Y2)") (class "Default")
      (node (ref "R39") (pin "P$1") (pinfunction "P$1_P$1") (pintype "passive"))
      (node (ref "R40") (pin "P$1") (pinfunction "P$1_P$1") (pintype "passive"))
      (node (ref "U$4") (pin "P4") (pinfunction "Y2_P4") (pintype "output"))
    )
    (net (code "38") (name "Net-(U$5-IN+)") (class "Default")
      (node (ref "C14") (pin "P$1") (pinfunction "P$1_P$1") (pintype "passive"))
      (node (ref "C8") (pin "P$1") (pinfunction "P$1_P$1") (pintype "passive"))
      (node (ref "R14") (pin "P$1") (pinfunction "P$1_P$1") (pintype "passive"))
      (node (ref "R15") (pin "P$1") (pinfunction "P$1_P$1") (pintype "passive"))
      (node (ref "U$5") (pin "3") (pinfunction "IN+_3") (pintype "bidirectional"))
    )
    (net (code "39") (name "Net-(U$5-IN-)") (class "Default")
      (node (ref "LASER71") (pin "TP") (pinfunction "TP_TP") (pintype "input"))
      (node (ref "R25") (pin "P$2") (pinfunction "P$2_P$2") (pintype "passive"))
      (node (ref "R38") (pin "P$2") (pinfunction "P$2_P$2") (pintype "passive"))
      (node (ref "U$5") (pin "4") (pinfunction "IN-_4") (pintype "bidirectional"))
      (node (ref "U1") (pin "P$2") (pinfunction "SOURCE_P$2") (pintype "bidirectional"))
    )
    (net (code "40") (name "Net-(U$5-OUT)") (class "Default")
      (node (ref "R16") (pin "P$1") (pinfunction "P$1_P$1") (pintype "passive"))
      (node (ref "U$5") (pin "1") (pinfunction "OUT_1") (pintype "bidirectional"))
    )
    (net (code "41") (name "Net-(U$7-P1)") (class "Default")
      (node (ref "C4") (pin "P$2") (pinfunction "P$2_P$2") (pintype "passive"))
      (node (ref "JP3") (pin "1") (pinfunction "1_1") (pintype "passive"))
      (node (ref "R23") (pin "P$1") (pinfunction "P$1_P$1") (pintype "passive"))
      (node (ref "TP3") (pin "TP") (pinfunction "TP_TP") (pintype "input"))
      (node (ref "U$7") (pin "1") (pinfunction "P1_1") (pintype "bidirectional"))
    )
    (net (code "42") (name "Net-(U$7-P4)") (class "Default")
      (node (ref "C4") (pin "P$1") (pinfunction "P$1_P$1") (pintype "passive"))
      (node (ref "R23") (pin "P$2") (pinfunction "P$2_P$2") (pintype "passive"))
      (node (ref "R32") (pin "P$2") (pinfunction "P$2_P$2") (pintype "passive"))
      (node (ref "R5") (pin "P$2") (pinfunction "P$2_P$2") (pintype "passive"))
      (node (ref "U$7") (pin "4") (pinfunction "P4_4") (pintype "bidirectional"))
    )
    (net (code "43") (name "Net-(U$8-FB)") (class "Default")
      (node (ref "C15") (pin "1") (pinfunction "1_1") (pintype "passive"))
      (node (ref "R17") (pin "P$1") (pinfunction "P$1_P$1") (pintype "passive"))
      (node (ref "R18") (pin "P$2") (pinfunction "P$2_P$2") (pintype "passive"))
      (node (ref "U$8") (pin "3") (pinfunction "FB_3") (pintype "bidirectional"))
    )
    (net (code "44") (name "Net-(U$8-SW)") (class "Default")
      (node (ref "U$14") (pin "P$2") (pinfunction "P$2_P$2") (pintype "bidirectional"))
      (node (ref "U$8") (pin "1") (pinfunction "SW_1") (pintype "bidirectional"))
      (node (ref "U$9") (pin "ANODE") (pinfunction "ANODE_ANODE") (pintype "bidirectional"))
    )
    (net (code "45") (name "Net-(U$8-{slash}SHDN)") (class "Default")
      (node (ref "R19") (pin "P$2") (pinfunction "P$2_P$2") (pintype "passive"))
      (node (ref "U$8") (pin "4") (pinfunction "/SHDN_4") (pintype "bidirectional"))
    )
    (net (code "46") (name "Net-(U$15-P1)") (class "Default")
      (node (ref "C5") (pin "P$2") (pinfunction "P$2_P$2") (pintype "passive"))
      (node (ref "JP3") (pin "2") (pinfunction "2_2") (pintype "passive"))
      (node (ref "R28") (pin "P$1") (pinfunction "P$1_P$1") (pintype "passive"))
      (node (ref "TP4") (pin "TP") (pinfunction "TP_TP") (pintype "input"))
      (node (ref "U$15") (pin "1") (pinfunction "P1_1") (pintype "bidirectional"))
    )
    (net (code "47") (name "Net-(U$15-P4)") (class "Default")
      (node (ref "C5") (pin "P$1") (pinfunction "P$1_P$1") (pintype "passive"))
      (node (ref "R24") (pin "P$2") (pinfunction "P$2_P$2") (pintype "passive"))
      (node (ref "R28") (pin "P$2") (pinfunction "P$2_P$2") (pintype "passive"))
      (node (ref "R8") (pin "P$2") (pinfunction "P$2_P$2") (pintype "passive"))
      (node (ref "U$15") (pin "4") (pinfunction "P4_4") (pintype "bidirectional"))
    )
    (net (code "48") (name "Net-(U$16-P1)") (class "Default")
      (node (ref "C6") (pin "P$2") (pinfunction "P$2_P$2") (pintype "passive"))
      (node (ref "JP3") (pin "3") (pinfunction "3_3") (pintype "passive"))
      (node (ref "R29") (pin "P$1") (pinfunction "P$1_P$1") (pintype "passive"))
      (node (ref "TP5") (pin "TP") (pinfunction "TP_TP") (pintype "input"))
      (node (ref "U$16") (pin "1") (pinfunction "P1_1") (pintype "bidirectional"))
    )
    (net (code "49") (name "Net-(U$16-P4)") (class "Default")
      (node (ref "C6") (pin "P$1") (pinfunction "P$1_P$1") (pintype "passive"))
      (node (ref "R27") (pin "P$2") (pinfunction "P$2_P$2") (pintype "passive"))
      (node (ref "R29") (pin "P$2") (pinfunction "P$2_P$2") (pintype "passive"))
      (node (ref "R34") (pin "P$2") (pinfunction "P$2_P$2") (pintype "passive"))
      (node (ref "U$16") (pin "4") (pinfunction "P4_4") (pintype "bidirectional"))
    )
    (net (code "50") (name "Net-(U$17-P1)") (class "Default")
      (node (ref "C7") (pin "P$2") (pinfunction "P$2_P$2") (pintype "passive"))
      (node (ref "JP3") (pin "4") (pinfunction "4_4") (pintype "passive"))
      (node (ref "R37") (pin "P$1") (pinfunction "P$1_P$1") (pintype "passive"))
      (node (ref "TP6") (pin "TP") (pinfunction "TP_TP") (pintype "input"))
      (node (ref "U$17") (pin "1") (pinfunction "P1_1") (pintype "bidirectional"))
    )
    (net (code "51") (name "Net-(U$17-P4)") (class "Default")
      (node (ref "C7") (pin "P$1") (pinfunction "P$1_P$1") (pintype "passive"))
      (node (ref "R36") (pin "P$2") (pinfunction "P$2_P$2") (pintype "passive"))
      (node (ref "R37") (pin "P$2") (pinfunction "P$2_P$2") (pintype "passive"))
      (node (ref "R41") (pin "P$2") (pinfunction "P$2_P$2") (pintype "passive"))
      (node (ref "U$17") (pin "4") (pinfunction "P4_4") (pintype "bidirectional"))
    )
    (net (code "52") (name "Net-(U1-GATE)") (class "Default")
      (node (ref "R16") (pin "P$2") (pinfunction "P$2_P$2") (pintype "passive"))
      (node (ref "U1") (pin "P$1") (pinfunction "GATE_P$1") (pintype "bidirectional"))
    )
    (net (code "53") (name "Net-(U2-EN)") (class "Default")
      (node (ref "C1") (pin "1") (pinfunction "1_1") (pintype "passive"))
      (node (ref "D1") (pin "CATHODE") (pinfunction "CATHODE_CATHODE") (pintype "bidirectional"))
      (node (ref "R35") (pin "P$2") (pinfunction "P$2_P$2") (pintype "passive"))
      (node (ref "U2") (pin "P$1") (pinfunction "VIN_P$1") (pintype "bidirectional"))
      (node (ref "U2") (pin "P$3") (pinfunction "EN_P$3") (pintype "bidirectional"))
    )
    (net (code "54") (name "Net-(U3-DRAIN)") (class "Default")
      (node (ref "R25") (pin "P$1") (pinfunction "P$1_P$1") (pintype "passive"))
      (node (ref "R42") (pin "P$2") (pinfunction "P$2_P$2") (pintype "passive"))
      (node (ref "U3") (pin "P$3") (pinfunction "DRAIN_P$3") (pintype "bidirectional"))
    )
    (net (code "55") (name "Net-(U3-GATE)") (class "Default")
      (node (ref "C16") (pin "P$1") (pinfunction "P$1_P$1") (pintype "passive"))
      (node (ref "R43") (pin "P$1") (pinfunction "P$1_P$1") (pintype "passive"))
      (node (ref "U3") (pin "P$1") (pinfunction "GATE_P$1") (pintype "bidirectional"))
    )
    (net (code "56") (name "SCK") (class "Default")
      (node (ref "JP5") (pin "3") (pinfunction "3_3") (pintype "passive"))
      (node (ref "U$1") (pin "P15") (pinfunction "PA5_P15") (pintype "bidirectional"))
    )
    (net (code "57") (name "SCL") (class "Default")
      (node (ref "JP6") (pin "4") (pinfunction "4_4") (pintype "passive"))
      (node (ref "U$1") (pin "P6") (pinfunction "PF1_P6") (pintype "bidirectional"))
    )
    (net (code "58") (name "SDA") (class "Default")
      (node (ref "JP6") (pin "2") (pinfunction "2_2") (pintype "passive"))
      (node (ref "U$1") (pin "P5") (pinfunction "PF0_P5") (pintype "bidirectional"))
    )
    (net (code "59") (name "SPI_CS") (class "Default")
      (node (ref "JP5") (pin "5") (pinfunction "5_5") (pintype "passive"))
      (node (ref "U$1") (pin "P18") (pinfunction "PB0_P18") (pintype "bidirectional"))
    )
    (net (code "60") (name "SWCLK") (class "Default")
      (node (ref "SWCLK71") (pin "TP") (pinfunction "TP_TP") (pintype "input"))
      (node (ref "U$1") (pin "P37") (pinfunction "PA14_P37") (pintype "bidirectional"))
    )
    (net (code "61") (name "SWDIO") (class "Default")
      (node (ref "SWDIO71") (pin "TP") (pinfunction "TP_TP") (pintype "input"))
      (node (ref "U$1") (pin "P34") (pinfunction "PA13_P34") (pintype "bidirectional"))
    )
    (net (code "62") (name "USB_DM") (class "Default")
      (node (ref "J1") (pin "2") (pinfunction "D-_2") (pintype "bidirectional"))
      (node (ref "U$1") (pin "P32") (pinfunction "PA11_P32") (pintype "bidirectional"))
      (node (ref "U$12") (pin "P1") (pinfunction "IO1_P1") (pintype "bidirectional"))
    )
    (net (code "63") (name "USB_DP") (class "Default")
      (node (ref "J1") (pin "3") (pinfunction "D+_3") (pintype "bidirectional"))
      (node (ref "U$1") (pin "P33") (pinfunction "PA12_P33") (pintype "bidirectional"))
      (node (ref "U$12") (pin "P3") (pinfunction "IO2_P3") (pintype "bidirectional"))
    )
    (net (code "64") (name "VUSB") (class "Default")
      (node (ref "C17") (pin "P$1") (pinfunction "P$1_P$1") (pintype "passive"))
      (node (ref "C18") (pin "P$1") (pinfunction "P$1_P$1") (pintype "passive"))
      (node (ref "C19") (pin "P$1") (pinfunction "P$1_P$1") (pintype "passive"))
      (node (ref "C20") (pin "P$1") (pinfunction "P$1_P$1") (pintype "passive"))
      (node (ref "C9") (pin "P$1") (pinfunction "P$1_P$1") (pintype "passive"))
      (node (ref "D1") (pin "ANODE") (pinfunction "ANODE_ANODE") (pintype "bidirectional"))
      (node (ref "L1") (pin "1") (pinfunction "1_1") (pintype "passive"))
      (node (ref "R19") (pin "P$1") (pinfunction "P$1_P$1") (pintype "passive"))
      (node (ref "U$10") (pin "CATHODE") (pinfunction "CATHODE_CATHODE") (pintype "bidirectional"))
      (node (ref "U$12") (pin "P5") (pinfunction "VCC_P5") (pintype "power_in"))
      (node (ref "U$13") (pin "CATHODE") (pinfunction "CATHODE_CATHODE") (pintype "bidirectional"))
      (node (ref "U$14") (pin "P$1") (pinfunction "P$1_P$1") (pintype "bidirectional"))
      (node (ref "U$15") (pin "2") (pinfunction "P2_2") (pintype "power_in"))
      (node (ref "U$16") (pin "2") (pinfunction "P2_2") (pintype "power_in"))
      (node (ref "U$17") (pin "2") (pinfunction "P2_2") (pintype "power_in"))
      (node (ref "U$7") (pin "2") (pinfunction "P2_2") (pintype "power_in"))
      (node (ref "U$8") (pin "5") (pinfunction "VIN_5") (pintype "bidirectional"))
      (node (ref "VUSB71") (pin "TP") (pinfunction "TP_TP") (pintype "input"))
    )
    (net (code "65") (name "XCOARSE_IN") (class "Default")
      (node (ref "R5") (pin "P$1") (pinfunction "P$1_P$1") (pintype "passive"))
      (node (ref "U$1") (pin "P38") (pinfunction "PA15_P38") (pintype "bidirectional"))
      (node (ref "U$2") (pin "P1") (pinfunction "A1_P1") (pintype "input"))
    )
    (net (code "66") (name "XFINE_IN") (class "Default")
      (node (ref "R31") (pin "P$1") (pinfunction "P$1_P$1") (pintype "passive"))
      (node (ref "R6") (pin "P$1") (pinfunction "P$1_P$1") (pintype "passive"))
      (node (ref "U$1") (pin "P39") (pinfunction "PB3_P39") (pintype "bidirectional"))
      (node (ref "U$2") (pin "P3") (pinfunction "A2_P3") (pintype "input"))
    )
    (net (code "67") (name "YCOARSE_IN") (class "Default")
      (node (ref "R27") (pin "P$1") (pinfunction "P$1_P$1") (pintype "passive"))
      (node (ref "U$1") (pin "P21") (pinfunction "PB10_P21") (pintype "bidirectional"))
      (node (ref "U$4") (pin "P1") (pinfunction "A1_P1") (pintype "input"))
    )
    (net (code "68") (name "YFINE_IN") (class "Default")
      (node (ref "R30") (pin "P$1") (pinfunction "P$1_P$1") (pintype "passive"))
      (node (ref "R33") (pin "P$1") (pinfunction "P$1_P$1") (pintype "passive"))
      (node (ref "U$1") (pin "P22") (pinfunction "PB11_P22") (pintype "bidirectional"))
      (node (ref "U$4") (pin "P3") (pinfunction "A2_P3") (pintype "input"))
    )
    (net (code "69") (name "unconnected-(U$1-PA4-PadP14)") (class "Default")
      (node (ref "U$1") (pin "P14") (pinfunction "PA4_P14") (pintype "bidirectional"))
    )
    (net (code "70") (name "unconnected-(U$1-PA8-PadP29)") (class "Default")
      (node (ref "U$1") (pin "P29") (pinfunction "PA8_P29") (pintype "bidirectional"))
    )
    (net (code "71") (name "unconnected-(U$1-PA9-PadP30)") (class "Default")
      (node (ref "U$1") (pin "P30") (pinfunction "PA9_P30") (pintype "bidirectional"))
    )
    (net (code "72") (name "unconnected-(U$1-PA10-PadP31)") (class "Default")
      (node (ref "U$1") (pin "P31") (pinfunction "PA10_P31") (pintype "bidirectional"))
    )
    (net (code "73") (name "unconnected-(U$1-PB1-PadP19)") (class "Default")
      (node (ref "U$1") (pin "P19") (pinfunction "PB1_P19") (pintype "bidirectional"))
    )
    (net (code "74") (name "unconnected-(U$1-PB2-PadP20)") (class "Default")
      (node (ref "U$1") (pin "P20") (pinfunction "PB2_P20") (pintype "bidirectional"))
    )
    (net (code "75") (name "unconnected-(U$1-PB6-PadP42)") (class "Default")
      (node (ref "U$1") (pin "P42") (pinfunction "PB6_P42") (pintype "bidirectional"))
    )
    (net (code "76") (name "unconnected-(U$1-PB7-PadP43)") (class "Default")
      (node (ref "U$1") (pin "P43") (pinfunction "PB7_P43") (pintype "bidirectional"))
    )
    (net (code "77") (name "unconnected-(U$1-PB8-PadP45)") (class "Default")
      (node (ref "U$1") (pin "P45") (pinfunction "PB8_P45") (pintype "bidirectional"))
    )
    (net (code "78") (name "unconnected-(U$1-PB9-PadP46)") (class "Default")
      (node (ref "U$1") (pin "P46") (pinfunction "PB9_P46") (pintype "bidirectional"))
    )
    (net (code "79") (name "unconnected-(U$1-PC13-PadP2)") (class "Default")
      (node (ref "U$1") (pin "P2") (pinfunction "PC13_P2") (pintype "bidirectional"))
    )
    (net (code "80") (name "unconnected-(U$1-PC14-PadP3)") (class "Default")
      (node (ref "U$1") (pin "P3") (pinfunction "PC14_P3") (pintype "bidirectional"))
    )
    (net (code "81") (name "unconnected-(U$1-PC15-PadP4)") (class "Default")
      (node (ref "U$1") (pin "P4") (pinfunction "PC15_P4") (pintype "bidirectional"))
    )
    (net (code "82") (name "unconnected-(U$12-IO3-PadP4)") (class "Default")
      (node (ref "U$12") (pin "P4") (pinfunction "IO3_P4") (pintype "bidirectional"))
    )
    (net (code "83") (name "unconnected-(U$12-IO4-PadP6)") (class "Default")
      (node (ref "U$12") (pin "P6") (pinfunction "IO4_P6") (pintype "bidirectional"))
    )
  )
)
